# Connectors.net
KiCad netlist of a schematic drawn in Altium Designer
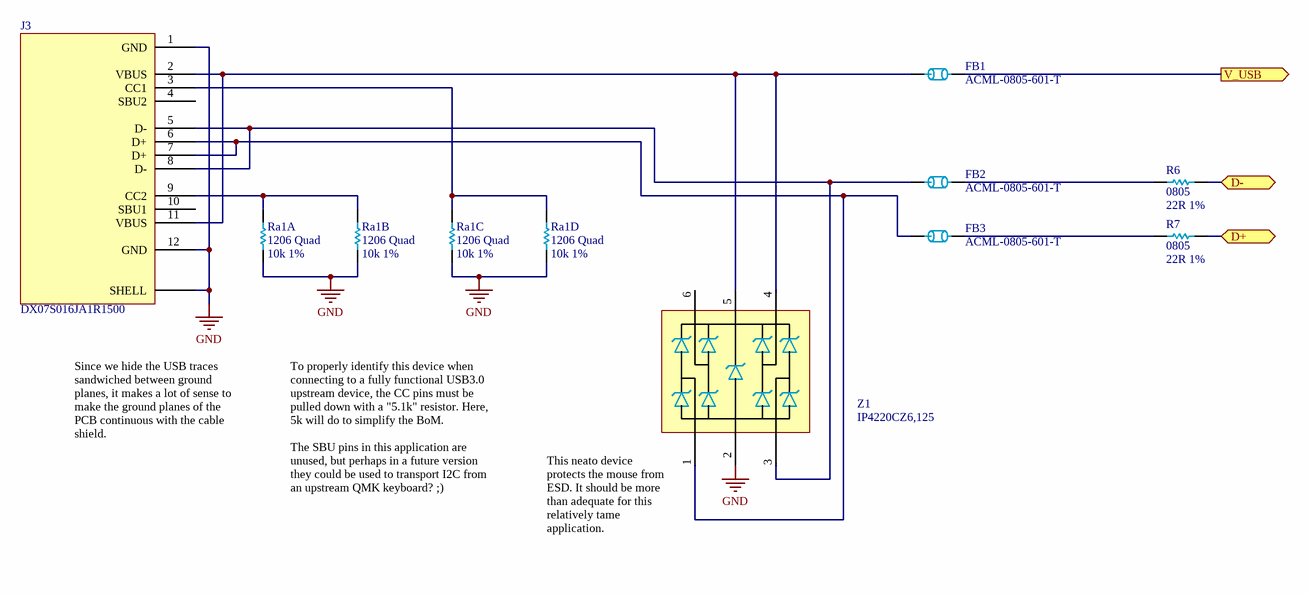
[diagram p0: Connectors.SchDoc]

(export (version "E")
  (design (tool "Eeschema 10.0.6"))
  (components
    (comp (ref "FB1")
      (value "ACML-0805-601-T")
      (footprint "0805")
      (description "FERRITE BEAD 600 OHM 0805 1LN")
      (libsource (lib "Chip_Passives") (part "ACML-0805-601-T"))
    )
    (comp (ref "FB2")
      (value "ACML-0805-601-T")
      (footprint "0805")
      (description "FERRITE BEAD 600 OHM 0805 1LN")
      (libsource (lib "Chip_Passives") (part "ACML-0805-601-T"))
    )
    (comp (ref "FB3")
      (value "ACML-0805-601-T")
      (footprint "0805")
      (description "FERRITE BEAD 600 OHM 0805 1LN")
      (libsource (lib "Chip_Passives") (part "ACML-0805-601-T"))
    )
    (comp (ref "J3")
      (value "DX07S016JA1R1500")
      (footprint "DX07S016JA1R1500")
      (libsource (lib "Connectors") (part "DX07S016JA1R1500"))
    )
    (comp (ref "R6")
      (value "0805")
      (footprint "0805")
      (description "Chip resistor")
      (fields (field (name "ALTIUM_VALUE") "22R 1%"))
      (libsource (lib "Chip_Passives") (part "Res 22R 1% 0805"))
    )
    (comp (ref "R7")
      (value "0805")
      (footprint "0805")
      (description "Chip resistor")
      (fields (field (name "ALTIUM_VALUE") "22R 1%"))
      (libsource (lib "Chip_Passives") (part "Res 22R 1% 0805"))
    )
    (comp (ref "Ra1")
      (value "1206 Quad")
      (footprint "4x 10k 1% - CAC-80P320X160-8M")
      (description "Chip resistor")
      (fields (field (name "ALTIUM_VALUE") "10k 1%"))
      (libsource (lib "Chip_Passives") (part "Quad Res 10k 1% 1206"))
    )
    (comp (ref "Z1")
      (value "IP4220CZ6,125")
      (footprint "PESD3V3S4UD - SOT95P275X110-6N")
      (description "TVS DIODE 5.5V 6TSOP (Low capacitance, USB)")
      (libsource (lib "Diodes") (part "IP4220CZ6,125"))
    )
  )
  (nets
    (net (code "1") (name "/D+") (class "Default")
      (node (ref "R7") (pin "2") (pinfunction "2_2") (pintype "passive"))
    )
    (net (code "2") (name "/D-") (class "Default")
      (node (ref "R6") (pin "2") (pinfunction "2_2") (pintype "passive"))
    )
    (net (code "3") (name "/V_USB") (class "Default")
      (node (ref "FB1") (pin "2") (pinfunction "2_2") (pintype "passive"))
    )
    (net (code "4") (name "GND") (class "Default")
      (node (ref "J3") (pin "1") (pinfunction "GND_1") (pintype "passive"))
      (node (ref "J3") (pin "12") (pinfunction "GND_12") (pintype "passive"))
      (node (ref "J3") (pin "SHELL") (pinfunction "SHELL_SHELL") (pintype "passive"))
      (node (ref "Ra1") (pin "1") (pinfunction "1_1") (pintype "passive"))
      (node (ref "Ra1") (pin "2") (pinfunction "2_2") (pintype "passive"))
      (node (ref "Ra1") (pin "3") (pinfunction "3_3") (pintype "passive"))
      (node (ref "Ra1") (pin "4") (pinfunction "4_4") (pintype "passive"))
      (node (ref "Z1") (pin "2") (pinfunction "2_2") (pintype "passive"))
    )
    (net (code "5") (name "Net-(FB1-Pad1)") (class "Default")
      (node (ref "FB1") (pin "1") (pinfunction "1_1") (pintype "passive"))
      (node (ref "J3") (pin "11") (pinfunction "VBUS_11") (pintype "passive"))
      (node (ref "J3") (pin "2") (pinfunction "VBUS_2") (pintype "passive"))
      (node (ref "Z1") (pin "4") (pinfunction "4_4") (pintype "passive"))
      (node (ref "Z1") (pin "5") (pinfunction "5_5") (pintype "passive"))
    )
    (net (code "6") (name "Net-(FB2-Pad1)") (class "Default")
      (node (ref "FB2") (pin "1") (pinfunction "1_1") (pintype "passive"))
      (node (ref "J3") (pin "5") (pinfunction "D-_5") (pintype "passive"))
      (node (ref "J3") (pin "8") (pinfunction "D-_8") (pintype "passive"))
      (node (ref "Z1") (pin "3") (pinfunction "3_3") (pintype "passive"))
    )
    (net (code "7") (name "Net-(FB2-Pad2)") (class "Default")
      (node (ref "FB2") (pin "2") (pinfunction "2_2") (pintype "passive"))
      (node (ref "R6") (pin "1") (pinfunction "1_1") (pintype "passive"))
    )
    (net (code "8") (name "Net-(FB3-Pad1)") (class "Default")
      (node (ref "FB3") (pin "1") (pinfunction "1_1") (pintype "passive"))
      (node (ref "J3") (pin "6") (pinfunction "D+_6") (pintype "passive"))
      (node (ref "J3") (pin "7") (pinfunction "D+_7") (pintype "passive"))
      (node (ref "Z1") (pin "1") (pinfunction "1_1") (pintype "passive"))
    )
    (net (code "9") (name "Net-(FB3-Pad2)") (class "Default")
      (node (ref "FB3") (pin "2") (pinfunction "2_2") (pintype "passive"))
      (node (ref "R7") (pin "1") (pinfunction "1_1") (pintype "passive"))
    )
    (net (code "10") (name "Net-(J3-CC1)") (class "Default")
      (node (ref "J3") (pin "3") (pinfunction "CC1_3") (pintype "passive"))
      (node (ref "Ra1") (pin "5") (pinfunction "5_5") (pintype "passive"))
      (node (ref "Ra1") (pin "6") (pinfunction "6_6") (pintype "passive"))
    )
    (net (code "11") (name "Net-(J3-CC2)") (class "Default")
      (node (ref "J3") (pin "9") (pinfunction "CC2_9") (pintype "passive"))
      (node (ref "Ra1") (pin "7") (pinfunction "7_7") (pintype "passive"))
      (node (ref "Ra1") (pin "8") (pinfunction "8_8") (pintype "passive"))
    )
    (net (code "12") (name "unconnected-(J3-SBU1-Pad10)") (class "Default")
      (node (ref "J3") (pin "10") (pinfunction "SBU1_10") (pintype "passive"))
    )
    (net (code "13") (name "unconnected-(J3-SBU2-Pad4)") (class "Default")
      (node (ref "J3") (pin "4") (pinfunction "SBU2_4") (pintype "passive"))
    )
    (net (code "14") (name "unconnected-(Z1-Pad6)") (class "Default")
      (node (ref "Z1") (pin "6") (pinfunction "6_6") (pintype "passive"))
    )
  )
)
